# monotribemidi.net
KiCad netlist of a schematic drawn in EAGLE
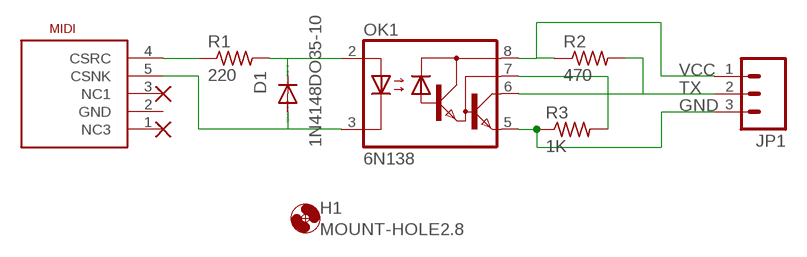
[diagram p0: schematic, sheet 1]

(export (version "E")
  (design (tool "Eeschema 10.0.6"))
  (components
    (comp (ref "D1")
      (value "1N4148DO35-10")
      (footprint "eagle-import:DO35-10")
      (libsource (lib "eagle-import") (part "1N4148DO35-10"))
    )
    (comp (ref "H1")
      (value "MOUNT-HOLE2.8")
      (footprint "eagle-import:2,8")
      (libsource (lib "eagle-import") (part "MOUNT-HOLE2.8"))
    )
    (comp (ref "JP1")
      (value "M03LOCK")
      (footprint "eagle-import:1X03_LOCK")
      (libsource (lib "eagle-import") (part "M03LOCK"))
    )
    (comp (ref "MIDI")
      (value "MIDI_CONN_FEMALE_SUPPORT")
      (footprint "eagle-import:DIN_5_FEMALE_SUPPORT")
      (libsource (lib "eagle-import") (part "MIDI_CONN_FEMALE_SUPPORT"))
    )
    (comp (ref "OK1")
      (value "6N138")
      (footprint "eagle-import:DIL08")
      (fields (field (name "MF") "VISHAY/TELEFUNKEN"))
      (libsource (lib "eagle-import") (part "6N138"))
    )
    (comp (ref "R1")
      (value "220")
      (footprint "eagle-import:0207_12")
      (libsource (lib "eagle-import") (part "R-US_0207/12"))
    )
    (comp (ref "R2")
      (value "470")
      (footprint "eagle-import:0207_12")
      (libsource (lib "eagle-import") (part "R-US_0207/12"))
    )
    (comp (ref "R3")
      (value "1K")
      (footprint "eagle-import:0207_12")
      (libsource (lib "eagle-import") (part "R-US_0207/12"))
    )
  )
  (nets
    (net (code "1") (name "/GND") (class "Default")
      (node (ref "JP1") (pin "3") (pinfunction "3_3") (pintype "passive"))
      (node (ref "OK1") (pin "5") (pinfunction "GND_5") (pintype "passive"))
      (node (ref "R3") (pin "1") (pinfunction "1_1") (pintype "passive"))
    )
    (net (code "2") (name "/TX") (class "Default")
      (node (ref "JP1") (pin "2") (pinfunction "2_2") (pintype "passive"))
      (node (ref "OK1") (pin "6") (pinfunction "VO_6") (pintype "passive"))
      (node (ref "R2") (pin "2") (pinfunction "2_2") (pintype "passive"))
    )
    (net (code "3") (name "/VCC") (class "Default")
      (node (ref "JP1") (pin "1") (pinfunction "1_1") (pintype "passive"))
      (node (ref "OK1") (pin "8") (pinfunction "VCC_8") (pintype "passive"))
      (node (ref "R2") (pin "1") (pinfunction "1_1") (pintype "passive"))
    )
    (net (code "4") (name "Net-(MIDI-CSNK)") (class "Default")
      (node (ref "D1") (pin "A") (pinfunction "A_A") (pintype "passive"))
      (node (ref "MIDI") (pin "5") (pinfunction "CSNK_5") (pintype "bidirectional"))
      (node (ref "OK1") (pin "3") (pinfunction "C_3") (pintype "passive"))
    )
    (net (code "5") (name "Net-(MIDI-CSRC)") (class "Default")
      (node (ref "MIDI") (pin "4") (pinfunction "CSRC_4") (pintype "bidirectional"))
      (node (ref "R1") (pin "1") (pinfunction "1_1") (pintype "passive"))
    )
    (net (code "6") (name "Net-(OK1-A)") (class "Default")
      (node (ref "D1") (pin "C") (pinfunction "C_C") (pintype "passive"))
      (node (ref "OK1") (pin "2") (pinfunction "A_2") (pintype "passive"))
      (node (ref "R1") (pin "2") (pinfunction "2_2") (pintype "passive"))
    )
    (net (code "7") (name "Net-(OK1-VB)") (class "Default")
      (node (ref "OK1") (pin "7") (pinfunction "VB_7") (pintype "passive"))
      (node (ref "R3") (pin "2") (pinfunction "2_2") (pintype "passive"))
    )
    (net (code "8") (name "unconnected-(MIDI-GND-Pad2)") (class "Default")
      (node (ref "MIDI") (pin "2") (pinfunction "GND_2") (pintype "bidirectional"))
    )
    (net (code "9") (name "unconnected-(MIDI-NC1-Pad3)") (class "Default")
      (node (ref "MIDI") (pin "3") (pinfunction "NC1_3") (pintype "bidirectional"))
    )
    (net (code "10") (name "unconnected-(MIDI-NC3-Pad1)") (class "Default")
      (node (ref "MIDI") (pin "1") (pinfunction "NC3_1") (pintype "bidirectional"))
    )
  )
)
